# ELSE_Perif.net
KiCad netlist of a schematic drawn in Altium Designer
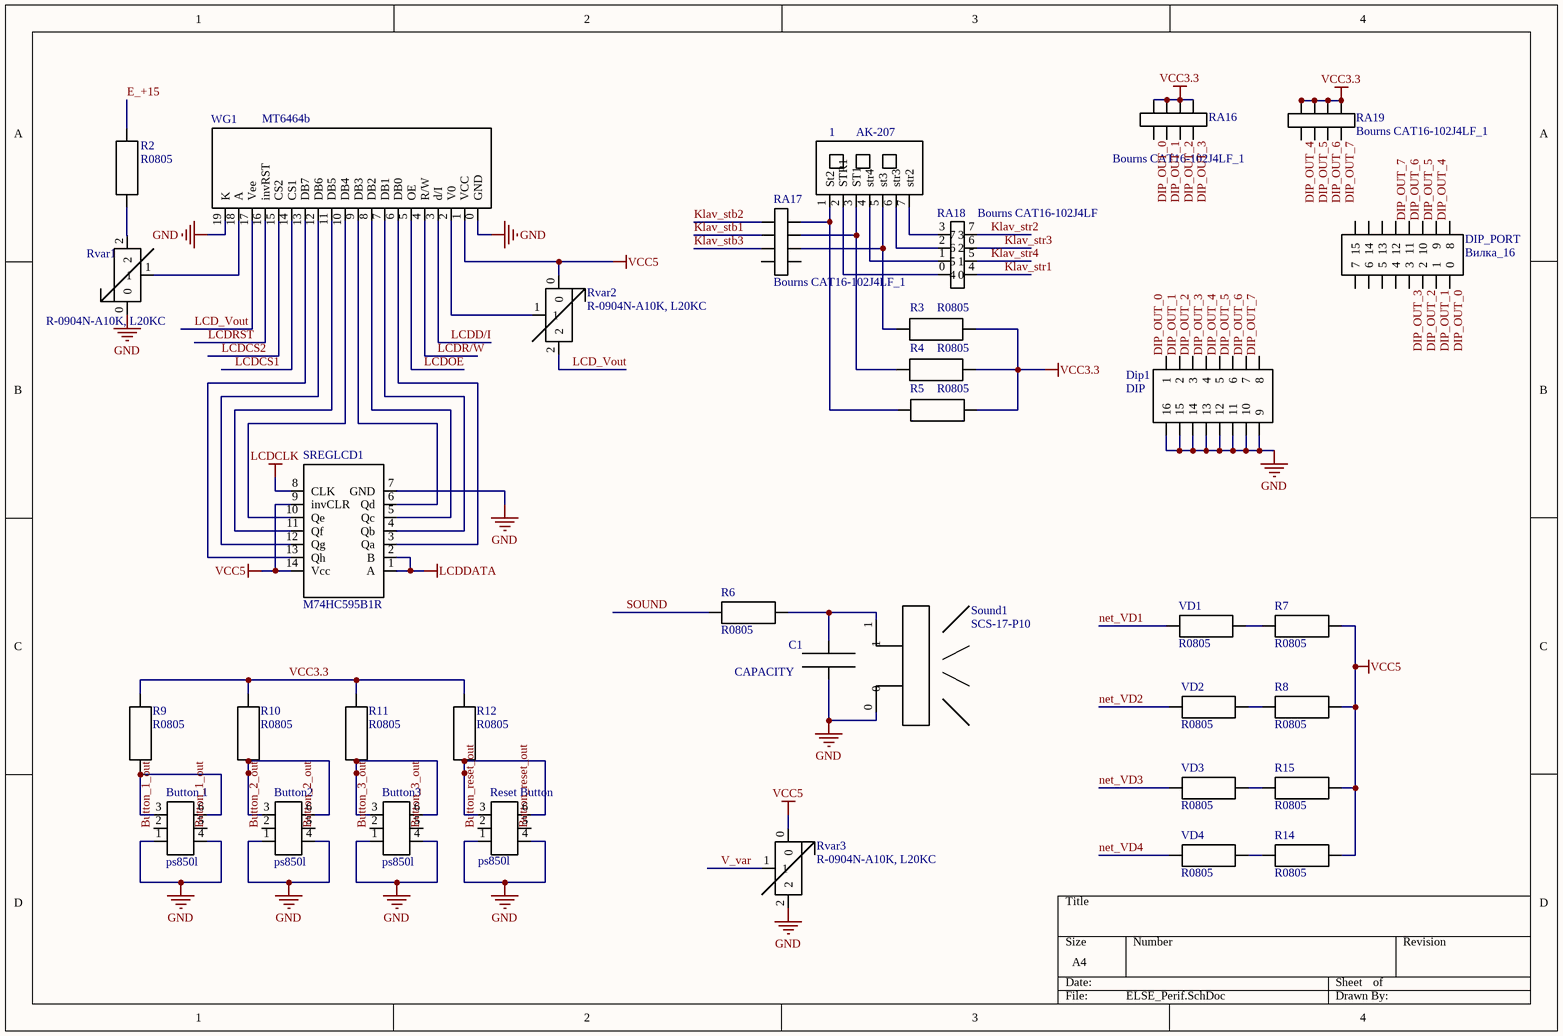
[diagram p0: ELSE_Perif.SchDoc]

(export (version "E")
  (design (tool "Eeschema 10.0.6"))
  (components
    (comp (ref "1") (value "AK-207") (footprint "PcbLib1:AK-207") (libsource (lib "Library") (part "AK-207")))
    (comp (ref "Button 1")
      (value "ps850l")
      (footprint "PcbLib1:ps850l")
      (libsource (lib "Library") (part "ps850l"))
    )
    (comp (ref "Button2")
      (value "ps850l")
      (footprint "PcbLib1:ps850l")
      (libsource (lib "Library") (part "ps850l"))
    )
    (comp (ref "Button3")
      (value "ps850l")
      (footprint "PcbLib1:ps850l")
      (libsource (lib "Library") (part "ps850l"))
    )
    (comp (ref "C1")
      (value "CAPACITY")
      (footprint "PcbLib1:R0805")
      (libsource (lib "Library") (part "CAPACITY"))
    )
    (comp (ref "Dip1") (value "DIP") (footprint "SWD1-8") (libsource (lib "Library") (part "DIP")))
    (comp (ref "DIP_PORT")
      (value "Вилка_16")
      (footprint "DS1013-16")
      (description "16_pin")
      (libsource (lib "Library") (part "DS1013-16"))
    )
    (comp (ref "R2") (value "R0805") (footprint "PcbLib1:R0805") (libsource (lib "Library") (part "R0805")))
    (comp (ref "R3") (value "R0805") (footprint "PcbLib1:R0805") (libsource (lib "Library") (part "R0805")))
    (comp (ref "R4") (value "R0805") (footprint "PcbLib1:R0805") (libsource (lib "Library") (part "R0805")))
    (comp (ref "R5") (value "R0805") (footprint "PcbLib1:R0805") (libsource (lib "Library") (part "R0805")))
    (comp (ref "R6") (value "R0805") (footprint "PcbLib1:R0805") (libsource (lib "Library") (part "R0805")))
    (comp (ref "R7") (value "R0805") (footprint "PcbLib1:R0805") (libsource (lib "Library") (part "R0805")))
    (comp (ref "R8") (value "R0805") (footprint "PcbLib1:R0805") (libsource (lib "Library") (part "R0805")))
    (comp (ref "R9") (value "R0805") (footprint "PcbLib1:R0805") (libsource (lib "Library") (part "R0805")))
    (comp (ref "R10") (value "R0805") (footprint "PcbLib1:R0805") (libsource (lib "Library") (part "R0805")))
    (comp (ref "R11") (value "R0805") (footprint "PcbLib1:R0805") (libsource (lib "Library") (part "R0805")))
    (comp (ref "R12") (value "R0805") (footprint "PcbLib1:R0805") (libsource (lib "Library") (part "R0805")))
    (comp (ref "R14") (value "R0805") (footprint "PcbLib1:R0805") (libsource (lib "Library") (part "R0805")))
    (comp (ref "R15") (value "R0805") (footprint "PcbLib1:R0805") (libsource (lib "Library") (part "R0805")))
    (comp (ref "RA16")
      (value "Bourns CAT16-102J4LF_1")
      (footprint "PcbLib1:CAT16-102J4LF_2")
      (libsource (lib "Library") (part "Bourns CAT16-102J4LF_1"))
    )
    (comp (ref "RA17")
      (value "Bourns CAT16-102J4LF_1")
      (footprint "PcbLib1:CAT16-102J4LF_2")
      (libsource (lib "Library") (part "Bourns CAT16-102J4LF_1"))
    )
    (comp (ref "RA18")
      (value "Bourns CAT16-102J4LF")
      (footprint "PcbLib1:CAT16-102J4LF")
      (libsource (lib "Library") (part "Bourns CAT16-102J4LF"))
    )
    (comp (ref "RA19")
      (value "Bourns CAT16-102J4LF_1")
      (footprint "PcbLib1:CAT16-102J4LF_2")
      (libsource (lib "Library") (part "Bourns CAT16-102J4LF_1"))
    )
    (comp (ref "Reset Button")
      (value "ps850l")
      (footprint "PcbLib1:ps850l")
      (libsource (lib "Library") (part "ps850l"))
    )
    (comp (ref "Rvar1")
      (value "R-0904N-A10K, L20KC")
      (footprint "PcbLib1:R-0904N-A10K, L20KC")
      (libsource (lib "Library") (part "R-0904N-A10K, L20KC"))
    )
    (comp (ref "Rvar2")
      (value "R-0904N-A10K, L20KC")
      (footprint "PcbLib1:R-0904N-A10K, L20KC")
      (libsource (lib "Library") (part "R-0904N-A10K, L20KC"))
    )
    (comp (ref "Rvar3")
      (value "R-0904N-A10K, L20KC")
      (footprint "PcbLib1:R-0904N-A10K, L20KC")
      (libsource (lib "Library") (part "R-0904N-A10K, L20KC"))
    )
    (comp (ref "Sound1")
      (value "SCS-17-P10")
      (footprint "PcbLib1:SCS-17-P10")
      (libsource (lib "Library") (part "SCS-17-P10"))
    )
    (comp (ref "SREGLCD1")
      (value "M74HC595B1R")
      (footprint "PcbLib1:SN74HC164DRX")
      (libsource (lib "Library") (part "M74HC595B1R"))
    )
    (comp (ref "VD1") (value "R0805") (footprint "PcbLib1:R0805") (libsource (lib "Library") (part "R0805")))
    (comp (ref "VD2") (value "R0805") (footprint "PcbLib1:R0805") (libsource (lib "Library") (part "R0805")))
    (comp (ref "VD3") (value "R0805") (footprint "PcbLib1:R0805") (libsource (lib "Library") (part "R0805")))
    (comp (ref "VD4") (value "R0805") (footprint "PcbLib1:R0805") (libsource (lib "Library") (part "R0805")))
    (comp (ref "WG1")
      (value "MT6464b")
      (footprint "PcbLib1:WG12864A")
      (libsource (lib "Library") (part "MT6464b"))
    )
  )
  (nets
    (net (code "1") (name "/Button_1_out") (class "Default")
      (node (ref "Button 1") (pin "2") (pinfunction "2_2") (pintype "passive"))
      (node (ref "Button 1") (pin "5") (pinfunction "5_5") (pintype "passive"))
    )
    (net (code "2") (name "/Button_2_out") (class "Default")
      (node (ref "Button2") (pin "2") (pinfunction "2_2") (pintype "passive"))
      (node (ref "Button2") (pin "5") (pinfunction "5_5") (pintype "passive"))
    )
    (net (code "3") (name "/Button_3_out") (class "Default")
      (node (ref "Button3") (pin "2") (pinfunction "2_2") (pintype "passive"))
      (node (ref "Button3") (pin "5") (pinfunction "5_5") (pintype "passive"))
    )
    (net (code "4") (name "/Button_reset_out") (class "Default")
      (node (ref "Reset Button") (pin "2") (pinfunction "2_2") (pintype "passive"))
      (node (ref "Reset Button") (pin "5") (pinfunction "5_5") (pintype "passive"))
    )
    (net (code "5") (name "/DIP_OUT_0") (class "Default")
      (node (ref "DIP_PORT") (pin "0") (pinfunction "0_0") (pintype "passive"))
      (node (ref "Dip1") (pin "1") (pinfunction "1_1") (pintype "passive"))
      (node (ref "RA16") (pin "0") (pinfunction "0_0") (pintype "passive"))
    )
    (net (code "6") (name "/DIP_OUT_1") (class "Default")
      (node (ref "DIP_PORT") (pin "1") (pinfunction "1_1") (pintype "passive"))
      (node (ref "Dip1") (pin "2") (pinfunction "2_2") (pintype "passive"))
      (node (ref "RA16") (pin "1") (pinfunction "1_1") (pintype "passive"))
    )
    (net (code "7") (name "/DIP_OUT_2") (class "Default")
      (node (ref "DIP_PORT") (pin "2") (pinfunction "2_2") (pintype "passive"))
      (node (ref "Dip1") (pin "3") (pinfunction "3_3") (pintype "passive"))
      (node (ref "RA16") (pin "2") (pinfunction "2_2") (pintype "passive"))
    )
    (net (code "8") (name "/DIP_OUT_3") (class "Default")
      (node (ref "DIP_PORT") (pin "3") (pinfunction "3_3") (pintype "passive"))
      (node (ref "Dip1") (pin "4") (pinfunction "4_4") (pintype "passive"))
      (node (ref "RA16") (pin "3") (pinfunction "3_3") (pintype "passive"))
    )
    (net (code "9") (name "/DIP_OUT_4") (class "Default")
      (node (ref "DIP_PORT") (pin "8") (pinfunction "8_8") (pintype "passive"))
      (node (ref "Dip1") (pin "5") (pinfunction "5_5") (pintype "passive"))
      (node (ref "RA19") (pin "0") (pinfunction "0_0") (pintype "passive"))
    )
    (net (code "10") (name "/DIP_OUT_5") (class "Default")
      (node (ref "DIP_PORT") (pin "9") (pinfunction "9_9") (pintype "passive"))
      (node (ref "Dip1") (pin "6") (pinfunction "6_6") (pintype "passive"))
      (node (ref "RA19") (pin "1") (pinfunction "1_1") (pintype "passive"))
    )
    (net (code "11") (name "/DIP_OUT_6") (class "Default")
      (node (ref "DIP_PORT") (pin "10") (pinfunction "10_10") (pintype "passive"))
      (node (ref "Dip1") (pin "7") (pinfunction "7_7") (pintype "passive"))
      (node (ref "RA19") (pin "2") (pinfunction "2_2") (pintype "passive"))
    )
    (net (code "12") (name "/DIP_OUT_7") (class "Default")
      (node (ref "DIP_PORT") (pin "11") (pinfunction "11_11") (pintype "passive"))
      (node (ref "Dip1") (pin "8") (pinfunction "8_8") (pintype "passive"))
      (node (ref "RA19") (pin "3") (pinfunction "3_3") (pintype "passive"))
    )
    (net (code "13") (name "/E_+15") (class "Default")
      (node (ref "R2") (pin "2") (pinfunction "2_2") (pintype "passive"))
    )
    (net (code "14") (name "/Klav_stb1") (class "Default")
      (node (ref "RA17") (pin "2") (pinfunction "2_2") (pintype "passive"))
    )
    (net (code "15") (name "/Klav_stb2") (class "Default")
      (node (ref "RA17") (pin "3") (pinfunction "3_3") (pintype "passive"))
    )
    (net (code "16") (name "/Klav_stb3") (class "Default")
      (node (ref "RA17") (pin "1") (pinfunction "1_1") (pintype "passive"))
    )
    (net (code "17") (name "/Klav_str1") (class "Default")
      (node (ref "RA18") (pin "4") (pinfunction "4_4") (pintype "passive"))
    )
    (net (code "18") (name "/Klav_str2") (class "Default")
      (node (ref "RA18") (pin "7") (pinfunction "7_7") (pintype "passive"))
    )
    (net (code "19") (name "/Klav_str3") (class "Default")
      (node (ref "RA18") (pin "6") (pinfunction "6_6") (pintype "passive"))
    )
    (net (code "20") (name "/Klav_str4") (class "Default")
      (node (ref "RA18") (pin "5") (pinfunction "5_5") (pintype "passive"))
    )
    (net (code "21") (name "/LCDCS1") (class "Default")
      (node (ref "WG1") (pin "14") (pinfunction "CS1_14") (pintype "passive"))
    )
    (net (code "22") (name "/LCDCS2") (class "Default")
      (node (ref "WG1") (pin "15") (pinfunction "CS2_15") (pintype "passive"))
    )
    (net (code "23") (name "/LCDD{slash}I") (class "Default")
      (node (ref "WG1") (pin "3") (pinfunction "d/I_3") (pintype "passive"))
    )
    (net (code "24") (name "/LCDOE") (class "Default")
      (node (ref "WG1") (pin "5") (pinfunction "OE_5") (pintype "passive"))
    )
    (net (code "25") (name "/LCDRST") (class "Default")
      (node (ref "WG1") (pin "16") (pinfunction "invRST_16") (pintype "passive"))
    )
    (net (code "26") (name "/LCDR{slash}W") (class "Default")
      (node (ref "WG1") (pin "4") (pinfunction "R/W_4") (pintype "passive"))
    )
    (net (code "27") (name "/LCD_Vout") (class "Default")
      (node (ref "Rvar2") (pin "2") (pinfunction "2_2") (pintype "passive"))
      (node (ref "WG1") (pin "17") (pinfunction "Vee_17") (pintype "passive"))
    )
    (net (code "28") (name "/SOUND") (class "Default")
      (node (ref "R6") (pin "1") (pinfunction "1_1") (pintype "passive"))
    )
    (net (code "29") (name "/V_var") (class "Default")
      (node (ref "Rvar3") (pin "1") (pinfunction "1_1") (pintype "passive"))
    )
    (net (code "30") (name "/net_VD1") (class "Default")
      (node (ref "VD1") (pin "1") (pinfunction "1_1") (pintype "passive"))
    )
    (net (code "31") (name "/net_VD2") (class "Default")
      (node (ref "VD2") (pin "1") (pinfunction "1_1") (pintype "passive"))
    )
    (net (code "32") (name "/net_VD3") (class "Default")
      (node (ref "VD3") (pin "1") (pinfunction "1_1") (pintype "passive"))
    )
    (net (code "33") (name "/net_VD4") (class "Default")
      (node (ref "VD4") (pin "1") (pinfunction "1_1") (pintype "passive"))
    )
    (net (code "34") (name "GND") (class "Default")
      (node (ref "Button 1") (pin "1") (pinfunction "1_1") (pintype "passive"))
      (node (ref "Button 1") (pin "4") (pinfunction "4_4") (pintype "passive"))
      (node (ref "Button2") (pin "1") (pinfunction "1_1") (pintype "passive"))
      (node (ref "Button2") (pin "4") (pinfunction "4_4") (pintype "passive"))
      (node (ref "Button3") (pin "1") (pinfunction "1_1") (pintype "passive"))
      (node (ref "Button3") (pin "4") (pinfunction "4_4") (pintype "passive"))
      (node (ref "C1") (pin "1") (pinfunction "1_1") (pintype "passive"))
      (node (ref "Dip1") (pin "10") (pinfunction "10_10") (pintype "passive"))
      (node (ref "Dip1") (pin "11") (pinfunction "11_11") (pintype "passive"))
      (node (ref "Dip1") (pin "12") (pinfunction "12_12") (pintype "passive"))
      (node (ref "Dip1") (pin "13") (pinfunction "13_13") (pintype "passive"))
      (node (ref "Dip1") (pin "14") (pinfunction "14_14") (pintype "passive"))
      (node (ref "Dip1") (pin "15") (pinfunction "15_15") (pintype "passive"))
      (node (ref "Dip1") (pin "16") (pinfunction "16_16") (pintype "passive"))
      (node (ref "Dip1") (pin "9") (pinfunction "9_9") (pintype "passive"))
      (node (ref "Reset Button") (pin "1") (pinfunction "1_1") (pintype "passive"))
      (node (ref "Reset Button") (pin "4") (pinfunction "4_4") (pintype "passive"))
      (node (ref "Rvar1") (pin "0") (pinfunction "0_0") (pintype "passive"))
      (node (ref "Rvar3") (pin "2") (pinfunction "2_2") (pintype "passive"))
      (node (ref "SREGLCD1") (pin "7") (pinfunction "GND_7") (pintype "passive"))
      (node (ref "Sound1") (pin "0") (pinfunction "0_0") (pintype "passive"))
      (node (ref "WG1") (pin "0") (pinfunction "GND_0") (pintype "passive"))
      (node (ref "WG1") (pin "19") (pinfunction "K_19") (pintype "passive"))
    )
    (net (code "35") (name "LCDCLK") (class "Default")
      (node (ref "SREGLCD1") (pin "8") (pinfunction "CLK_8") (pintype "passive"))
    )
    (net (code "36") (name "LCDDATA") (class "Default")
      (node (ref "SREGLCD1") (pin "1") (pinfunction "A_1") (pintype "passive"))
      (node (ref "SREGLCD1") (pin "2") (pinfunction "B_2") (pintype "passive"))
    )
    (net (code "37") (name "Net-(1-ST1)") (class "Default")
      (node (ref "1") (pin "3") (pinfunction "ST1_3") (pintype "passive"))
      (node (ref "R4") (pin "2") (pinfunction "2_2") (pintype "passive"))
      (node (ref "RA17") (pin "5") (pinfunction "5_5") (pintype "passive"))
    )
    (net (code "38") (name "Net-(1-STR1)") (class "Default")
      (node (ref "1") (pin "2") (pinfunction "STR1_2") (pintype "passive"))
      (node (ref "RA18") (pin "0") (pinfunction "0_0") (pintype "passive"))
    )
    (net (code "39") (name "Net-(1-St2)") (class "Default")
      (node (ref "1") (pin "1") (pinfunction "St2_1") (pintype "passive"))
      (node (ref "R5") (pin "2") (pinfunction "2_2") (pintype "passive"))
      (node (ref "RA17") (pin "4") (pinfunction "4_4") (pintype "passive"))
    )
    (net (code "40") (name "Net-(1-st3)") (class "Default")
      (node (ref "1") (pin "5") (pinfunction "st3_5") (pintype "passive"))
      (node (ref "R3") (pin "2") (pinfunction "2_2") (pintype "passive"))
      (node (ref "RA17") (pin "6") (pinfunction "6_6") (pintype "passive"))
    )
    (net (code "41") (name "Net-(1-str2)") (class "Default")
      (node (ref "1") (pin "7") (pinfunction "str2_7") (pintype "passive"))
      (node (ref "RA18") (pin "3") (pinfunction "3_3") (pintype "passive"))
    )
    (net (code "42") (name "Net-(1-str3)") (class "Default")
      (node (ref "1") (pin "6") (pinfunction "str3_6") (pintype "passive"))
      (node (ref "RA18") (pin "2") (pinfunction "2_2") (pintype "passive"))
    )
    (net (code "43") (name "Net-(1-str4)") (class "Default")
      (node (ref "1") (pin "4") (pinfunction "str4_4") (pintype "passive"))
      (node (ref "RA18") (pin "1") (pinfunction "1_1") (pintype "passive"))
    )
    (net (code "44") (name "Net-(Button 1-Pad3)") (class "Default")
      (node (ref "Button 1") (pin "3") (pinfunction "3_3") (pintype "passive"))
      (node (ref "Button 1") (pin "6") (pinfunction "6_6") (pintype "passive"))
      (node (ref "R9") (pin "2") (pinfunction "2_2") (pintype "passive"))
    )
    (net (code "45") (name "Net-(Button2-Pad3)") (class "Default")
      (node (ref "Button2") (pin "3") (pinfunction "3_3") (pintype "passive"))
      (node (ref "Button2") (pin "6") (pinfunction "6_6") (pintype "passive"))
      (node (ref "R10") (pin "2") (pinfunction "2_2") (pintype "passive"))
    )
    (net (code "46") (name "Net-(Button3-Pad3)") (class "Default")
      (node (ref "Button3") (pin "3") (pinfunction "3_3") (pintype "passive"))
      (node (ref "Button3") (pin "6") (pinfunction "6_6") (pintype "passive"))
      (node (ref "R11") (pin "2") (pinfunction "2_2") (pintype "passive"))
    )
    (net (code "47") (name "Net-(C1-Pad2)") (class "Default")
      (node (ref "C1") (pin "2") (pinfunction "2_2") (pintype "passive"))
      (node (ref "R6") (pin "2") (pinfunction "2_2") (pintype "passive"))
      (node (ref "Sound1") (pin "1") (pinfunction "1_1") (pintype "passive"))
    )
    (net (code "48") (name "Net-(R2-Pad1)") (class "Default")
      (node (ref "R2") (pin "1") (pinfunction "1_1") (pintype "passive"))
      (node (ref "Rvar1") (pin "2") (pinfunction "2_2") (pintype "passive"))
    )
    (net (code "49") (name "Net-(R7-Pad1)") (class "Default")
      (node (ref "R7") (pin "1") (pinfunction "1_1") (pintype "passive"))
      (node (ref "VD1") (pin "2") (pinfunction "2_2") (pintype "passive"))
    )
    (net (code "50") (name "Net-(R8-Pad1)") (class "Default")
      (node (ref "R8") (pin "1") (pinfunction "1_1") (pintype "passive"))
      (node (ref "VD2") (pin "2") (pinfunction "2_2") (pintype "passive"))
    )
    (net (code "51") (name "Net-(R12-Pad2)") (class "Default")
      (node (ref "R12") (pin "2") (pinfunction "2_2") (pintype "passive"))
      (node (ref "Reset Button") (pin "3") (pinfunction "3_3") (pintype "passive"))
      (node (ref "Reset Button") (pin "6") (pinfunction "6_6") (pintype "passive"))
    )
    (net (code "52") (name "Net-(R14-Pad1)") (class "Default")
      (node (ref "R14") (pin "1") (pinfunction "1_1") (pintype "passive"))
      (node (ref "VD4") (pin "2") (pinfunction "2_2") (pintype "passive"))
    )
    (net (code "53") (name "Net-(R15-Pad1)") (class "Default")
      (node (ref "R15") (pin "1") (pinfunction "1_1") (pintype "passive"))
      (node (ref "VD3") (pin "2") (pinfunction "2_2") (pintype "passive"))
    )
    (net (code "54") (name "Net-(SREGLCD1-Qa)") (class "Default")
      (node (ref "SREGLCD1") (pin "3") (pinfunction "Qa_3") (pintype "passive"))
      (node (ref "WG1") (pin "6") (pinfunction "DB0_6") (pintype "passive"))
    )
    (net (code "55") (name "Net-(SREGLCD1-Qb)") (class "Default")
      (node (ref "SREGLCD1") (pin "4") (pinfunction "Qb_4") (pintype "passive"))
      (node (ref "WG1") (pin "7") (pinfunction "DB1_7") (pintype "passive"))
    )
    (net (code "56") (name "Net-(SREGLCD1-Qc)") (class "Default")
      (node (ref "SREGLCD1") (pin "5") (pinfunction "Qc_5") (pintype "passive"))
      (node (ref "WG1") (pin "8") (pinfunction "DB2_8") (pintype "passive"))
    )
    (net (code "57") (name "Net-(SREGLCD1-Qd)") (class "Default")
      (node (ref "SREGLCD1") (pin "6") (pinfunction "Qd_6") (pintype "passive"))
      (node (ref "WG1") (pin "9") (pinfunction "DB3_9") (pintype "passive"))
    )
    (net (code "58") (name "Net-(SREGLCD1-Qe)") (class "Default")
      (node (ref "SREGLCD1") (pin "10") (pinfunction "Qe_10") (pintype "passive"))
      (node (ref "WG1") (pin "10") (pinfunction "DB4_10") (pintype "passive"))
    )
    (net (code "59") (name "Net-(SREGLCD1-Qf)") (class "Default")
      (node (ref "SREGLCD1") (pin "11") (pinfunction "Qf_11") (pintype "passive"))
      (node (ref "WG1") (pin "11") (pinfunction "DB5_11") (pintype "passive"))
    )
    (net (code "60") (name "Net-(SREGLCD1-Qg)") (class "Default")
      (node (ref "SREGLCD1") (pin "12") (pinfunction "Qg_12") (pintype "passive"))
      (node (ref "WG1") (pin "12") (pinfunction "DB6_12") (pintype "passive"))
    )
    (net (code "61") (name "Net-(SREGLCD1-Qh)") (class "Default")
      (node (ref "SREGLCD1") (pin "13") (pinfunction "Qh_13") (pintype "passive"))
      (node (ref "WG1") (pin "13") (pinfunction "DB7_13") (pintype "passive"))
    )
    (net (code "62") (name "Net-(WG1-A)") (class "Default")
      (node (ref "Rvar1") (pin "1") (pinfunction "1_1") (pintype "passive"))
      (node (ref "WG1") (pin "18") (pinfunction "A_18") (pintype "passive"))
    )
    (net (code "63") (name "Net-(WG1-V0)") (class "Default")
      (node (ref "Rvar2") (pin "1") (pinfunction "1_1") (pintype "passive"))
      (node (ref "WG1") (pin "2") (pinfunction "V0_2") (pintype "passive"))
    )
    (net (code "64") (name "VCC3.3") (class "Default")
      (node (ref "R10") (pin "1") (pinfunction "1_1") (pintype "passive"))
      (node (ref "R11") (pin "1") (pinfunction "1_1") (pintype "passive"))
      (node (ref "R12") (pin "1") (pinfunction "1_1") (pintype "passive"))
      (node (ref "R3") (pin "1") (pinfunction "1_1") (pintype "passive"))
      (node (ref "R4") (pin "1") (pinfunction "1_1") (pintype "passive"))
      (node (ref "R5") (pin "1") (pinfunction "1_1") (pintype "passive"))
      (node (ref "R9") (pin "1") (pinfunction "1_1") (pintype "passive"))
      (node (ref "RA16") (pin "4") (pinfunction "4_4") (pintype "passive"))
      (node (ref "RA16") (pin "5") (pinfunction "5_5") (pintype "passive"))
      (node (ref "RA16") (pin "6") (pinfunction "6_6") (pintype "passive"))
      (node (ref "RA16") (pin "7") (pinfunction "7_7") (pintype "passive"))
      (node (ref "RA19") (pin "4") (pinfunction "4_4") (pintype "passive"))
      (node (ref "RA19") (pin "5") (pinfunction "5_5") (pintype "passive"))
      (node (ref "RA19") (pin "6") (pinfunction "6_6") (pintype "passive"))
      (node (ref "RA19") (pin "7") (pinfunction "7_7") (pintype "passive"))
    )
    (net (code "65") (name "VCC5") (class "Default")
      (node (ref "R14") (pin "2") (pinfunction "2_2") (pintype "passive"))
      (node (ref "R15") (pin "2") (pinfunction "2_2") (pintype "passive"))
      (node (ref "R7") (pin "2") (pinfunction "2_2") (pintype "passive"))
      (node (ref "R8") (pin "2") (pinfunction "2_2") (pintype "passive"))
      (node (ref "Rvar2") (pin "0") (pinfunction "0_0") (pintype "passive"))
      (node (ref "Rvar3") (pin "0") (pinfunction "0_0") (pintype "passive"))
      (node (ref "SREGLCD1") (pin "14") (pinfunction "Vcc_14") (pintype "passive"))
      (node (ref "SREGLCD1") (pin "9") (pinfunction "invCLR_9") (pintype "passive"))
      (node (ref "WG1") (pin "1") (pinfunction "VCC_1") (pintype "passive"))
    )
    (net (code "66") (name "unconnected-(DIP_PORT-Pad4)") (class "Default")
      (node (ref "DIP_PORT") (pin "4") (pinfunction "4_4") (pintype "passive"))
    )
    (net (code "67") (name "unconnected-(DIP_PORT-Pad5)") (class "Default")
      (node (ref "DIP_PORT") (pin "5") (pinfunction "5_5") (pintype "passive"))
    )
    (net (code "68") (name "unconnected-(DIP_PORT-Pad6)") (class "Default")
      (node (ref "DIP_PORT") (pin "6") (pinfunction "6_6") (pintype "passive"))
    )
    (net (code "69") (name "unconnected-(DIP_PORT-Pad7)") (class "Default")
      (node (ref "DIP_PORT") (pin "7") (pinfunction "7_7") (pintype "passive"))
    )
    (net (code "70") (name "unconnected-(DIP_PORT-Pad12)") (class "Default")
      (node (ref "DIP_PORT") (pin "12") (pinfunction "12_12") (pintype "passive"))
    )
    (net (code "71") (name "unconnected-(DIP_PORT-Pad13)") (class "Default")
      (node (ref "DIP_PORT") (pin "13") (pinfunction "13_13") (pintype "passive"))
    )
    (net (code "72") (name "unconnected-(DIP_PORT-Pad14)") (class "Default")
      (node (ref "DIP_PORT") (pin "14") (pinfunction "14_14") (pintype "passive"))
    )
    (net (code "73") (name "unconnected-(DIP_PORT-Pad15)") (class "Default")
      (node (ref "DIP_PORT") (pin "15") (pinfunction "15_15") (pintype "passive"))
    )
    (net (code "74") (name "unconnected-(RA17-Pad0)") (class "Default")
      (node (ref "RA17") (pin "0") (pinfunction "0_0") (pintype "passive"))
    )
    (net (code "75") (name "unconnected-(RA17-Pad7)") (class "Default")
      (node (ref "RA17") (pin "7") (pinfunction "7_7") (pintype "passive"))
    )
  )
)
